# morseSounder.net
KiCad netlist of a schematic drawn in EAGLE
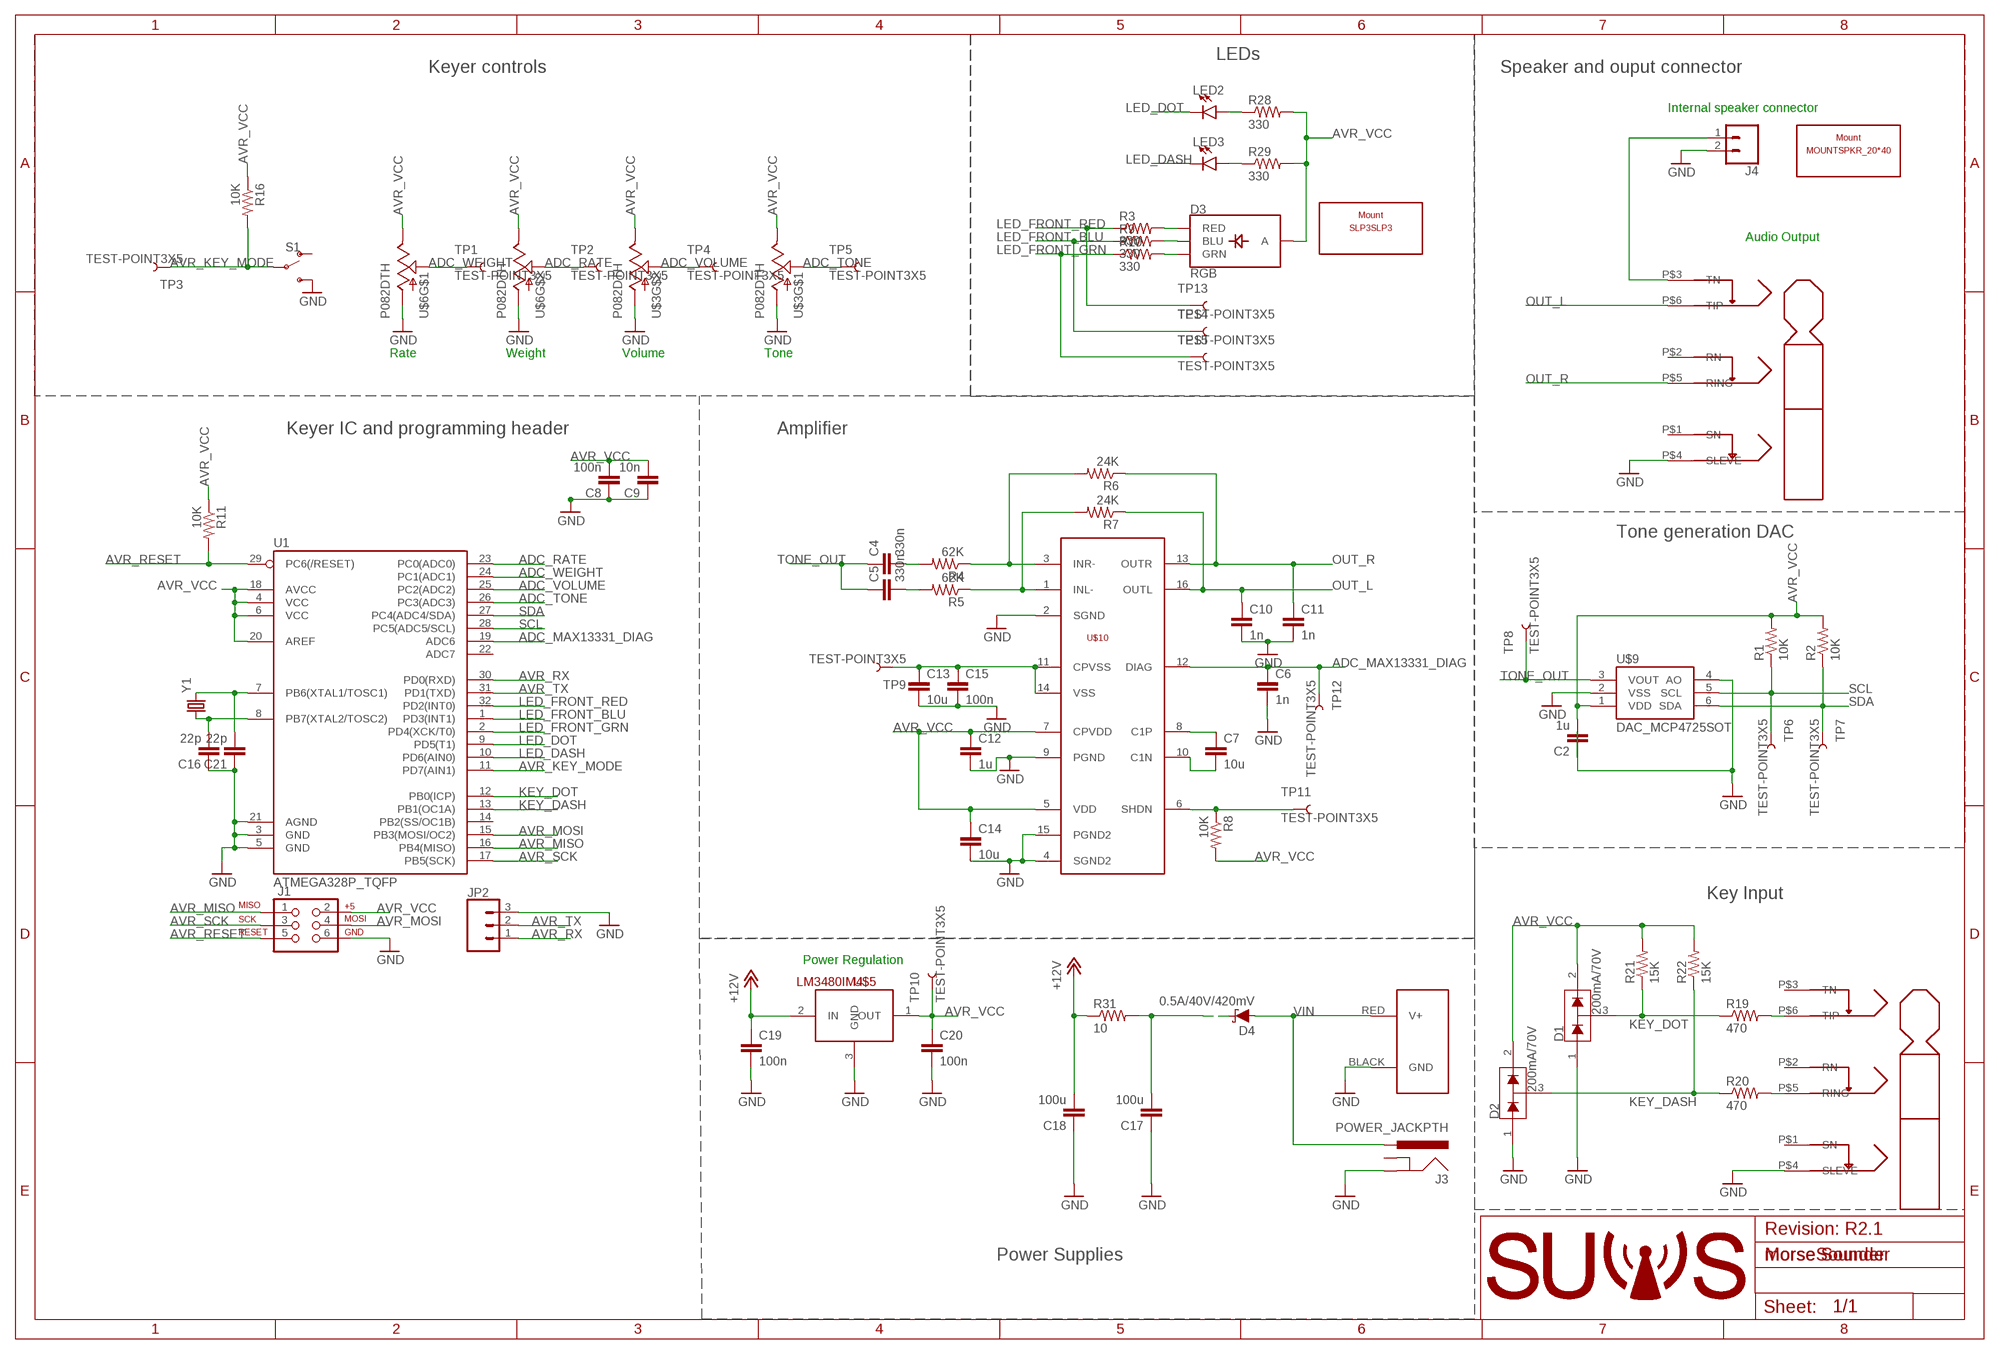
[diagram p0: schematic, sheet 1]

(export (version "E")
  (design (tool "Eeschema 10.0.6"))
  (components
    (comp (ref "C2")
      (value "1u")
      (footprint "eagle-import:0805")
      (libsource (lib "eagle-import") (part "CAP0805"))
    )
    (comp (ref "C4")
      (value "330n")
      (footprint "eagle-import:0805")
      (libsource (lib "eagle-import") (part "CAP0805"))
    )
    (comp (ref "C5")
      (value "330n")
      (footprint "eagle-import:0805")
      (libsource (lib "eagle-import") (part "CAP0805"))
    )
    (comp (ref "C6")
      (value "1n")
      (footprint "eagle-import:0805")
      (libsource (lib "eagle-import") (part "CAP0805"))
    )
    (comp (ref "C7")
      (value "10u")
      (footprint "eagle-import:0805")
      (libsource (lib "eagle-import") (part "CAP0805"))
    )
    (comp (ref "C8")
      (value "100n")
      (footprint "eagle-import:0805")
      (libsource (lib "eagle-import") (part "CAP0805"))
    )
    (comp (ref "C9")
      (value "10n")
      (footprint "eagle-import:0805")
      (libsource (lib "eagle-import") (part "CAP0805"))
    )
    (comp (ref "C10")
      (value "1n")
      (footprint "eagle-import:0805")
      (libsource (lib "eagle-import") (part "CAP0805"))
    )
    (comp (ref "C11")
      (value "1n")
      (footprint "eagle-import:0805")
      (libsource (lib "eagle-import") (part "CAP0805"))
    )
    (comp (ref "C12")
      (value "1u")
      (footprint "eagle-import:0805")
      (libsource (lib "eagle-import") (part "CAP0805"))
    )
    (comp (ref "C13")
      (value "10u")
      (footprint "eagle-import:0805")
      (libsource (lib "eagle-import") (part "CAP0805"))
    )
    (comp (ref "C14")
      (value "10u")
      (footprint "eagle-import:0805")
      (libsource (lib "eagle-import") (part "CAP0805"))
    )
    (comp (ref "C15")
      (value "100n")
      (footprint "eagle-import:0805")
      (libsource (lib "eagle-import") (part "CAP0805"))
    )
    (comp (ref "C16")
      (value "22p")
      (footprint "eagle-import:0805")
      (libsource (lib "eagle-import") (part "CAP0805"))
    )
    (comp (ref "C17")
      (value "100u")
      (footprint "eagle-import:0805")
      (libsource (lib "eagle-import") (part "CAP0805"))
    )
    (comp (ref "C18")
      (value "100u")
      (footprint "eagle-import:0805")
      (libsource (lib "eagle-import") (part "CAP0805"))
    )
    (comp (ref "C19")
      (value "100n")
      (footprint "eagle-import:0805")
      (libsource (lib "eagle-import") (part "CAP0805"))
    )
    (comp (ref "C20")
      (value "100n")
      (footprint "eagle-import:0805")
      (libsource (lib "eagle-import") (part "CAP0805"))
    )
    (comp (ref "C21")
      (value "22p")
      (footprint "eagle-import:0805")
      (libsource (lib "eagle-import") (part "CAP0805"))
    )
    (comp (ref "D1")
      (value "200mA/70V")
      (footprint "eagle-import:SOT23-3")
      (libsource (lib "eagle-import") (part "BAV99"))
    )
    (comp (ref "D2")
      (value "200mA/70V")
      (footprint "eagle-import:SOT23-3")
      (libsource (lib "eagle-import") (part "BAV99"))
    )
    (comp (ref "D3")
      (value "RGB")
      (footprint "eagle-import:P-LCC-4-3")
      (libsource (lib "eagle-import") (part "LED-RGB-CACREE"))
    )
    (comp (ref "D4")
      (value "0.5A/40V/420mV")
      (footprint "eagle-import:SOD-323")
      (libsource (lib "eagle-import") (part "DIODE-SCHOTTKY-PMEG4005EJ"))
    )
    (comp (ref "J1")
      (value "AVR_SPI_PRG_6PTH")
      (footprint "eagle-import:2X3")
      (libsource (lib "eagle-import") (part "AVR_SPI_PRG_6PTH"))
    )
    (comp (ref "J2")
      (value "POWERPOLE_POWER25A_HORIZONTAL_G2")
      (footprint "eagle-import:POWERPOLE_PAIR_25A_HORIZ_G2")
      (libsource (lib "eagle-import") (part "POWERPOLE_POWER25A_HORIZONTAL_G2"))
    )
    (comp (ref "J3")
      (value "POWER_JACKPTH")
      (footprint "eagle-import:POWER_JACK_PTH")
      (libsource (lib "eagle-import") (part "POWER_JACKPTH"))
    )
    (comp (ref "J4")
      (value "CONN_02")
      (footprint "eagle-import:1X02")
      (libsource (lib "eagle-import") (part "CONN_02"))
    )
    (comp (ref "JP2")
      (value "CONN_03")
      (footprint "eagle-import:1X03")
      (libsource (lib "eagle-import") (part "CONN_03"))
    )
    (comp (ref "LED2")
      (value "LED-RED1206")
      (footprint "eagle-import:LED-1206")
      (libsource (lib "eagle-import") (part "LED-RED1206"))
    )
    (comp (ref "LED3")
      (value "LED-RED1206")
      (footprint "eagle-import:LED-1206")
      (libsource (lib "eagle-import") (part "LED-RED1206"))
    )
    (comp (ref "R1")
      (value "10K")
      (footprint "eagle-import:0805")
      (libsource (lib "eagle-import") (part "RESISTOR0805-RES"))
    )
    (comp (ref "R2")
      (value "10K")
      (footprint "eagle-import:0805")
      (libsource (lib "eagle-import") (part "RESISTOR0805-RES"))
    )
    (comp (ref "R3")
      (value "330")
      (footprint "eagle-import:0805")
      (libsource (lib "eagle-import") (part "RESISTOR0805-RES"))
    )
    (comp (ref "R4")
      (value "62K")
      (footprint "eagle-import:0805")
      (libsource (lib "eagle-import") (part "RESISTOR0805-RES"))
    )
    (comp (ref "R5")
      (value "62K")
      (footprint "eagle-import:0805")
      (libsource (lib "eagle-import") (part "RESISTOR0805-RES"))
    )
    (comp (ref "R6")
      (value "24K")
      (footprint "eagle-import:0805")
      (libsource (lib "eagle-import") (part "RESISTOR0805-RES"))
    )
    (comp (ref "R7")
      (value "24K")
      (footprint "eagle-import:0805")
      (libsource (lib "eagle-import") (part "RESISTOR0805-RES"))
    )
    (comp (ref "R8")
      (value "10K")
      (footprint "eagle-import:0805")
      (libsource (lib "eagle-import") (part "RESISTOR0805-RES"))
    )
    (comp (ref "R9")
      (value "330")
      (footprint "eagle-import:0805")
      (libsource (lib "eagle-import") (part "RESISTOR0805-RES"))
    )
    (comp (ref "R10")
      (value "330")
      (footprint "eagle-import:0805")
      (libsource (lib "eagle-import") (part "RESISTOR0805-RES"))
    )
    (comp (ref "R11")
      (value "10K")
      (footprint "eagle-import:0805")
      (libsource (lib "eagle-import") (part "RESISTOR0805-RES"))
    )
    (comp (ref "R16")
      (value "10K")
      (footprint "eagle-import:0805")
      (libsource (lib "eagle-import") (part "RESISTOR0805-RES"))
    )
    (comp (ref "R19")
      (value "470")
      (footprint "eagle-import:0805")
      (libsource (lib "eagle-import") (part "RESISTOR0805-RES"))
    )
    (comp (ref "R20")
      (value "470")
      (footprint "eagle-import:0805")
      (libsource (lib "eagle-import") (part "RESISTOR0805-RES"))
    )
    (comp (ref "R21")
      (value "15K")
      (footprint "eagle-import:0805")
      (libsource (lib "eagle-import") (part "RESISTOR0805-RES"))
    )
    (comp (ref "R22")
      (value "15K")
      (footprint "eagle-import:0805")
      (libsource (lib "eagle-import") (part "RESISTOR0805-RES"))
    )
    (comp (ref "R28")
      (value "330")
      (footprint "eagle-import:0805")
      (libsource (lib "eagle-import") (part "RESISTOR0805-RES"))
    )
    (comp (ref "R29")
      (value "330")
      (footprint "eagle-import:0805")
      (libsource (lib "eagle-import") (part "RESISTOR0805-RES"))
    )
    (comp (ref "R31")
      (value "10")
      (footprint "eagle-import:0805")
      (libsource (lib "eagle-import") (part "RESISTOR0805-RES"))
    )
    (comp (ref "S1")
      (value "SWITCH-SPDTTE-1825232-1")
      (footprint "eagle-import:TE-1825232-1")
      (libsource (lib "eagle-import") (part "SWITCH-SPDTTE-1825232-1"))
    )
    (comp (ref "TP1")
      (value "TEST-POINT3X5")
      (footprint "eagle-import:PAD.03X.05")
      (libsource (lib "eagle-import") (part "TEST-POINT3X5"))
    )
    (comp (ref "TP2")
      (value "TEST-POINT3X5")
      (footprint "eagle-import:PAD.03X.05")
      (libsource (lib "eagle-import") (part "TEST-POINT3X5"))
    )
    (comp (ref "TP3")
      (value "TEST-POINT3X5")
      (footprint "eagle-import:PAD.03X.05")
      (libsource (lib "eagle-import") (part "TEST-POINT3X5"))
    )
    (comp (ref "TP4")
      (value "TEST-POINT3X5")
      (footprint "eagle-import:PAD.03X.05")
      (libsource (lib "eagle-import") (part "TEST-POINT3X5"))
    )
    (comp (ref "TP5")
      (value "TEST-POINT3X5")
      (footprint "eagle-import:PAD.03X.05")
      (libsource (lib "eagle-import") (part "TEST-POINT3X5"))
    )
    (comp (ref "TP6")
      (value "TEST-POINT3X5")
      (footprint "eagle-import:PAD.03X.05")
      (libsource (lib "eagle-import") (part "TEST-POINT3X5"))
    )
    (comp (ref "TP7")
      (value "TEST-POINT3X5")
      (footprint "eagle-import:PAD.03X.05")
      (libsource (lib "eagle-import") (part "TEST-POINT3X5"))
    )
    (comp (ref "TP8")
      (value "TEST-POINT3X5")
      (footprint "eagle-import:PAD.03X.05")
      (libsource (lib "eagle-import") (part "TEST-POINT3X5"))
    )
    (comp (ref "TP9")
      (value "TEST-POINT3X5")
      (footprint "eagle-import:PAD.03X.05")
      (libsource (lib "eagle-import") (part "TEST-POINT3X5"))
    )
    (comp (ref "TP10")
      (value "TEST-POINT3X5")
      (footprint "eagle-import:PAD.03X.05")
      (libsource (lib "eagle-import") (part "TEST-POINT3X5"))
    )
    (comp (ref "TP11")
      (value "TEST-POINT3X5")
      (footprint "eagle-import:PAD.03X.05")
      (libsource (lib "eagle-import") (part "TEST-POINT3X5"))
    )
    (comp (ref "TP12")
      (value "TEST-POINT3X5")
      (footprint "eagle-import:PAD.03X.05")
      (libsource (lib "eagle-import") (part "TEST-POINT3X5"))
    )
    (comp (ref "TP13")
      (value "TEST-POINT3X5")
      (footprint "eagle-import:PAD.03X.05")
      (libsource (lib "eagle-import") (part "TEST-POINT3X5"))
    )
    (comp (ref "TP14")
      (value "TEST-POINT3X5")
      (footprint "eagle-import:PAD.03X.05")
      (libsource (lib "eagle-import") (part "TEST-POINT3X5"))
    )
    (comp (ref "TP15")
      (value "TEST-POINT3X5")
      (footprint "eagle-import:PAD.03X.05")
      (libsource (lib "eagle-import") (part "TEST-POINT3X5"))
    )
    (comp (ref "U$1")
      (value "NRJ6HH")
      (footprint "eagle-import:NRJ6HH")
      (libsource (lib "eagle-import") (part "NRJ6HH"))
    )
    (comp (ref "U$2")
      (value "NRJ6HH")
      (footprint "eagle-import:NRJ6HH")
      (libsource (lib "eagle-import") (part "NRJ6HH"))
    )
    (comp (ref "U$3")
      (value "P082DTH")
      (footprint "eagle-import:P082D")
      (libsource (lib "eagle-import") (part "P082DTH"))
    )
    (comp (ref "U$4")
      (value "MOUNTSPKR_20*40")
      (footprint "eagle-import:SKR_MNT")
      (libsource (lib "eagle-import") (part "MOUNTSPKR_2040"))
    )
    (comp (ref "U$5")
      (value "LM3480IM4")
      (footprint "eagle-import:SOT23-3")
      (libsource (lib "eagle-import") (part "LM3480IM4"))
    )
    (comp (ref "U$6")
      (value "P082DTH")
      (footprint "eagle-import:P082D")
      (libsource (lib "eagle-import") (part "P082DTH"))
    )
    (comp (ref "U$7")
      (value "LOGO_SUWSLOGO_LARGE")
      (footprint "eagle-import:LOGO_SUWS")
      (libsource (lib "eagle-import") (part "LOGO_SUWSLOGO_LARGE"))
    )
    (comp (ref "U$8")
      (value "SLP3SLP3")
      (footprint "eagle-import:SLP-3")
      (libsource (lib "eagle-import") (part "SLP3SLP3"))
    )
    (comp (ref "U$9")
      (value "DAC_MCP4725SOT")
      (footprint "eagle-import:SOT23-6")
      (libsource (lib "eagle-import") (part "DAC_MCP4725SOT"))
    )
    (comp (ref "U$10")
      (value "MAX13331")
      (footprint "eagle-import:SSOP16")
      (libsource (lib "eagle-import") (part "MAX13331"))
    )
    (comp (ref "U1")
      (value "ATMEGA328P_TQFP")
      (footprint "eagle-import:TQFP32-08")
      (libsource (lib "eagle-import") (part "ATMEGA328P_TQFP"))
    )
    (comp (ref "Y1")
      (value "CRYSTALHC49UV")
      (footprint "eagle-import:HC49U-V")
      (libsource (lib "eagle-import") (part "CRYSTALHC49UV"))
    )
  )
  (nets
    (net (code "1") (name "+12V") (class "Default")
      (node (ref "C18") (pin "2") (pinfunction "2_2") (pintype "passive"))
      (node (ref "C19") (pin "1") (pinfunction "1_1") (pintype "passive"))
      (node (ref "R31") (pin "1") (pinfunction "1_1") (pintype "passive"))
      (node (ref "U$5") (pin "2") (pinfunction "IN_2") (pintype "bidirectional"))
    )
    (net (code "2") (name "/ADC_MAX13331_DIAG") (class "Default")
      (node (ref "C6") (pin "1") (pinfunction "1_1") (pintype "passive"))
      (node (ref "TP12") (pin "P$1") (pinfunction "1_P$1") (pintype "bidirectional"))
      (node (ref "U$10") (pin "12") (pinfunction "DIAG_12") (pintype "bidirectional"))
      (node (ref "U1") (pin "19") (pinfunction "ADC6_19") (pintype "bidirectional"))
    )
    (net (code "3") (name "/ADC_RATE") (class "Default")
      (node (ref "TP2") (pin "P$1") (pinfunction "1_P$1") (pintype "bidirectional"))
      (node (ref "U$6") (pin "R2") (pinfunction "S_R2") (pintype "passive"))
      (node (ref "U1") (pin "23") (pinfunction "PC0(ADC0)_23") (pintype "bidirectional"))
    )
    (net (code "4") (name "/ADC_TONE") (class "Default")
      (node (ref "TP5") (pin "P$1") (pinfunction "1_P$1") (pintype "bidirectional"))
      (node (ref "U$3") (pin "F2") (pinfunction "S_F2") (pintype "passive"))
      (node (ref "U1") (pin "26") (pinfunction "PC3(ADC3)_26") (pintype "bidirectional"))
    )
    (net (code "5") (name "/ADC_VOLUME") (class "Default")
      (node (ref "TP4") (pin "P$1") (pinfunction "1_P$1") (pintype "bidirectional"))
      (node (ref "U$3") (pin "R2") (pinfunction "S_R2") (pintype "passive"))
      (node (ref "U1") (pin "25") (pinfunction "PC2(ADC2)_25") (pintype "bidirectional"))
    )
    (net (code "6") (name "/ADC_WEIGHT") (class "Default")
      (node (ref "TP1") (pin "P$1") (pinfunction "1_P$1") (pintype "bidirectional"))
      (node (ref "U$6") (pin "F2") (pinfunction "S_F2") (pintype "passive"))
      (node (ref "U1") (pin "24") (pinfunction "PC1(ADC1)_24") (pintype "bidirectional"))
    )
    (net (code "7") (name "/AVR_KEY_MODE") (class "Default")
      (node (ref "R16") (pin "2") (pinfunction "2_2") (pintype "passive"))
      (node (ref "S1") (pin "2") (pinfunction "P_2") (pintype "passive"))
      (node (ref "TP3") (pin "P$1") (pinfunction "1_P$1") (pintype "bidirectional"))
      (node (ref "U1") (pin "11") (pinfunction "PD7(AIN1)_11") (pintype "bidirectional"))
    )
    (net (code "8") (name "/AVR_MISO") (class "Default")
      (node (ref "J1") (pin "1") (pinfunction "1_1") (pintype "passive"))
      (node (ref "U1") (pin "16") (pinfunction "PB4(MISO)_16") (pintype "bidirectional"))
    )
    (net (code "9") (name "/AVR_MOSI") (class "Default")
      (node (ref "J1") (pin "4") (pinfunction "4_4") (pintype "passive"))
      (node (ref "U1") (pin "15") (pinfunction "PB3(MOSI/OC2)_15") (pintype "bidirectional"))
    )
    (net (code "10") (name "/AVR_RESET") (class "Default")
      (node (ref "J1") (pin "5") (pinfunction "5_5") (pintype "passive"))
      (node (ref "R11") (pin "2") (pinfunction "2_2") (pintype "passive"))
      (node (ref "U1") (pin "29") (pinfunction "PC6(/RESET)_29") (pintype "bidirectional"))
    )
    (net (code "11") (name "/AVR_RX") (class "Default")
      (node (ref "JP2") (pin "1") (pinfunction "1_1") (pintype "passive"))
      (node (ref "U1") (pin "30") (pinfunction "PD0(RXD)_30") (pintype "bidirectional"))
    )
    (net (code "12") (name "/AVR_SCK") (class "Default")
      (node (ref "J1") (pin "3") (pinfunction "3_3") (pintype "passive"))
      (node (ref "U1") (pin "17") (pinfunction "PB5(SCK)_17") (pintype "bidirectional"))
    )
    (net (code "13") (name "/AVR_TX") (class "Default")
      (node (ref "JP2") (pin "2") (pinfunction "2_2") (pintype "passive"))
      (node (ref "U1") (pin "31") (pinfunction "PD1(TXD)_31") (pintype "bidirectional"))
    )
    (net (code "14") (name "/AVR_VCC") (class "Default")
      (node (ref "C12") (pin "1") (pinfunction "1_1") (pintype "passive"))
      (node (ref "C14") (pin "1") (pinfunction "1_1") (pintype "passive"))
      (node (ref "C2") (pin "2") (pinfunction "2_2") (pintype "passive"))
      (node (ref "C20") (pin "1") (pinfunction "1_1") (pintype "passive"))
      (node (ref "C8") (pin "2") (pinfunction "2_2") (pintype "passive"))
      (node (ref "C9") (pin "2") (pinfunction "2_2") (pintype "passive"))
      (node (ref "D1") (pin "2") (pinfunction "C2_2") (pintype "bidirectional"))
      (node (ref "D2") (pin "2") (pinfunction "C2_2") (pintype "bidirectional"))
      (node (ref "D3") (pin "1") (pinfunction "A_1") (pintype "bidirectional"))
      (node (ref "J1") (pin "2") (pinfunction "2_2") (pintype "passive"))
      (node (ref "R1") (pin "2") (pinfunction "2_2") (pintype "passive"))
      (node (ref "R11") (pin "1") (pinfunction "1_1") (pintype "passive"))
      (node (ref "R16") (pin "1") (pinfunction "1_1") (pintype "passive"))
      (node (ref "R2") (pin "2") (pinfunction "2_2") (pintype "passive"))
      (node (ref "R21") (pin "2") (pinfunction "2_2") (pintype "passive"))
      (node (ref "R22") (pin "2") (pinfunction "2_2") (pintype "passive"))
      (node (ref "R28") (pin "2") (pinfunction "2_2") (pintype "passive"))
      (node (ref "R29") (pin "2") (pinfunction "2_2") (pintype "passive"))
      (node (ref "R8") (pin "2") (pinfunction "2_2") (pintype "passive"))
      (node (ref "TP10") (pin "P$1") (pinfunction "1_P$1") (pintype "bidirectional"))
      (node (ref "U$10") (pin "5") (pinfunction "VDD_5") (pintype "bidirectional"))
      (node (ref "U$10") (pin "7") (pinfunction "CPVDD_7") (pintype "bidirectional"))
      (node (ref "U$3") (pin "F3") (pinfunction "E_F3") (pintype "passive"))
      (node (ref "U$3") (pin "R3") (pinfunction "E_R3") (pintype "passive"))
      (node (ref "U$5") (pin "1") (pinfunction "OUT_1") (pintype "bidirectional"))
      (node (ref "U$6") (pin "F3") (pinfunction "E_F3") (pintype "passive"))
      (node (ref "U$6") (pin "R3") (pinfunction "E_R3") (pintype "passive"))
      (node (ref "U$9") (pin "1") (pinfunction "VDD_1") (pintype "bidirectional"))
      (node (ref "U1") (pin "18") (pinfunction "AVCC_18") (pintype "bidirectional"))
      (node (ref "U1") (pin "20") (pinfunction "AREF_20") (pintype "bidirectional"))
      (node (ref "U1") (pin "4") (pinfunction "VCC_4") (pintype "bidirectional"))
      (node (ref "U1") (pin "6") (pinfunction "VCC_6") (pintype "bidirectional"))
    )
    (net (code "15") (name "/KEY_DASH") (class "Default")
      (node (ref "D2") (pin "3") (pinfunction "COM_3") (pintype "bidirectional"))
      (node (ref "R20") (pin "1") (pinfunction "1_1") (pintype "passive"))
      (node (ref "R22") (pin "1") (pinfunction "1_1") (pintype "passive"))
      (node (ref "U1") (pin "13") (pinfunction "PB1(OC1A)_13") (pintype "bidirectional"))
    )
    (net (code "16") (name "/KEY_DOT") (class "Default")
      (node (ref "D1") (pin "3") (pinfunction "COM_3") (pintype "bidirectional"))
      (node (ref "R19") (pin "1") (pinfunction "1_1") (pintype "passive"))
      (node (ref "R21") (pin "1") (pinfunction "1_1") (pintype "passive"))
      (node (ref "U1") (pin "12") (pinfunction "PB0(ICP)_12") (pintype "bidirectional"))
    )
    (net (code "17") (name "/LED_DASH") (class "Default")
      (node (ref "LED3") (pin "C") (pinfunction "C_C") (pintype "passive"))
      (node (ref "U1") (pin "10") (pinfunction "PD6(AIN0)_10") (pintype "bidirectional"))
    )
    (net (code "18") (name "/LED_DOT") (class "Default")
      (node (ref "LED2") (pin "C") (pinfunction "C_C") (pintype "passive"))
      (node (ref "U1") (pin "9") (pinfunction "PD5(T1)_9") (pintype "bidirectional"))
    )
    (net (code "19") (name "/LED_FRONT_BLU") (class "Default")
      (node (ref "R9") (pin "1") (pinfunction "1_1") (pintype "passive"))
      (node (ref "TP14") (pin "P$1") (pinfunction "1_P$1") (pintype "bidirectional"))
      (node (ref "U1") (pin "1") (pinfunction "PD3(INT1)_1") (pintype "bidirectional"))
    )
    (net (code "20") (name "/LED_FRONT_GRN") (class "Default")
      (node (ref "R10") (pin "1") (pinfunction "1_1") (pintype "passive"))
      (node (ref "TP15") (pin "P$1") (pinfunction "1_P$1") (pintype "bidirectional"))
      (node (ref "U1") (pin "2") (pinfunction "PD4(XCK/T0)_2") (pintype "bidirectional"))
    )
    (net (code "21") (name "/LED_FRONT_RED") (class "Default")
      (node (ref "R3") (pin "1") (pinfunction "1_1") (pintype "passive"))
      (node (ref "TP13") (pin "P$1") (pinfunction "1_P$1") (pintype "bidirectional"))
      (node (ref "U1") (pin "32") (pinfunction "PD2(INT0)_32") (pintype "bidirectional"))
    )
    (net (code "22") (name "/OUT_L") (class "Default")
      (node (ref "C10") (pin "1") (pinfunction "1_1") (pintype "passive"))
      (node (ref "R7") (pin "1") (pinfunction "1_1") (pintype "passive"))
      (node (ref "U$10") (pin "16") (pinfunction "OUTL_16") (pintype "bidirectional"))
      (node (ref "U$2") (pin "P$6") (pinfunction "TIP_P$6") (pintype "bidirectional"))
    )
    (net (code "23") (name "/OUT_R") (class "Default")
      (node (ref "C11") (pin "1") (pinfunction "1_1") (pintype "passive"))
      (node (ref "R6") (pin "1") (pinfunction "1_1") (pintype "passive"))
      (node (ref "U$10") (pin "13") (pinfunction "OUTR_13") (pintype "bidirectional"))
      (node (ref "U$2") (pin "P$5") (pinfunction "RING_P$5") (pintype "bidirectional"))
    )
    (net (code "24") (name "/SCL") (class "Default")
      (node (ref "R1") (pin "1") (pinfunction "1_1") (pintype "passive"))
      (node (ref "TP6") (pin "P$1") (pinfunction "1_P$1") (pintype "bidirectional"))
      (node (ref "U$9") (pin "5") (pinfunction "SCL_5") (pintype "bidirectional"))
      (node (ref "U1") (pin "28") (pinfunction "PC5(ADC5/SCL)_28") (pintype "bidirectional"))
    )
    (net (code "25") (name "/SDA") (class "Default")
      (node (ref "R2") (pin "1") (pinfunction "1_1") (pintype "passive"))
      (node (ref "TP7") (pin "P$1") (pinfunction "1_P$1") (pintype "bidirectional"))
      (node (ref "U$9") (pin "6") (pinfunction "SDA_6") (pintype "bidirectional"))
      (node (ref "U1") (pin "27") (pinfunction "PC4(ADC4/SDA)_27") (pintype "bidirectional"))
    )
    (net (code "26") (name "/TONE_OUT") (class "Default")
      (node (ref "C4") (pin "1") (pinfunction "1_1") (pintype "passive"))
      (node (ref "C5") (pin "1") (pinfunction "1_1") (pintype "passive"))
      (node (ref "TP8") (pin "P$1") (pinfunction "1_P$1") (pintype "bidirectional"))
      (node (ref "U$9") (pin "3") (pinfunction "VOUT_3") (pintype "bidirectional"))
    )
    (net (code "27") (name "/VIN") (class "Default")
      (node (ref "D4") (pin "A") (pinfunction "A_A") (pintype "passive"))
      (node (ref "J2") (pin "RED") (pinfunction "V+_RED") (pintype "power_in"))
      (node (ref "J3") (pin "PWR") (pinfunction "PWR_PWR") (pintype "bidirectional"))
    )
    (net (code "28") (name "GND") (class "Default")
      (node (ref "C10") (pin "2") (pinfunction "2_2") (pintype "passive"))
      (node (ref "C11") (pin "2") (pinfunction "2_2") (pintype "passive"))
      (node (ref "C12") (pin "2") (pinfunction "2_2") (pintype "passive"))
      (node (ref "C13") (pin "2") (pinfunction "2_2") (pintype "passive"))
      (node (ref "C14") (pin "2") (pinfunction "2_2") (pintype "passive"))
      (node (ref "C15") (pin "2") (pinfunction "2_2") (pintype "passive"))
      (node (ref "C16") (pin "1") (pinfunction "1_1") (pintype "passive"))
      (node (ref "C17") (pin "1") (pinfunction "1_1") (pintype "passive"))
      (node (ref "C18") (pin "1") (pinfunction "1_1") (pintype "passive"))
      (node (ref "C19") (pin "2") (pinfunction "2_2") (pintype "passive"))
      (node (ref "C2") (pin "1") (pinfunction "1_1") (pintype "passive"))
      (node (ref "C20") (pin "2") (pinfunction "2_2") (pintype "passive"))
      (node (ref "C21") (pin "1") (pinfunction "1_1") (pintype "passive"))
      (node (ref "C6") (pin "2") (pinfunction "2_2") (pintype "passive"))
      (node (ref "C8") (pin "1") (pinfunction "1_1") (pintype "passive"))
      (node (ref "C9") (pin "1") (pinfunction "1_1") (pintype "passive"))
      (node (ref "D1") (pin "1") (pinfunction "A1_1") (pintype "bidirectional"))
      (node (ref "D2") (pin "1") (pinfunction "A1_1") (pintype "bidirectional"))
      (node (ref "J1") (pin "6") (pinfunction "6_6") (pintype "passive"))
      (node (ref "J2") (pin "BLACK") (pinfunction "GND_BLACK") (pintype "power_in"))
      (node (ref "J3") (pin "GND") (pinfunction "GND_GND") (pintype "bidirectional"))
      (node (ref "J4") (pin "2") (pinfunction "2_2") (pintype "passive"))
      (node (ref "JP2") (pin "3") (pinfunction "3_3") (pintype "passive"))
      (node (ref "S1") (pin "3") (pinfunction "S_3") (pintype "passive"))
      (node (ref "U$1") (pin "P$4") (pinfunction "SLEVE_P$4") (pintype "bidirectional"))
      (node (ref "U$10") (pin "15") (pinfunction "PGND2_15") (pintype "bidirectional"))
      (node (ref "U$10") (pin "2") (pinfunction "SGND_2") (pintype "bidirectional"))
      (node (ref "U$10") (pin "4") (pinfunction "SGND2_4") (pintype "bidirectional"))
      (node (ref "U$10") (pin "9") (pinfunction "PGND_9") (pintype "bidirectional"))
      (node (ref "U$2") (pin "P$4") (pinfunction "SLEVE_P$4") (pintype "bidirectional"))
      (node (ref "U$3") (pin "F1") (pinfunction "A_F1") (pintype "passive"))
      (node (ref "U$3") (pin "R1") (pinfunction "A_R1") (pintype "passive"))
      (node (ref "U$5") (pin "3") (pinfunction "GND_3") (pintype "bidirectional"))
      (node (ref "U$6") (pin "F1") (pinfunction "A_F1") (pintype "passive"))
      (node (ref "U$6") (pin "R1") (pinfunction "A_R1") (pintype "passive"))
      (node (ref "U$9") (pin "2") (pinfunction "VSS_2") (pintype "bidirectional"))
      (node (ref "U$9") (pin "4") (pinfunction "AO_4") (pintype "bidirectional"))
      (node (ref "U1") (pin "21") (pinfunction "AGND_21") (pintype "bidirectional"))
      (node (ref "U1") (pin "3") (pinfunction "GND_3") (pintype "bidirectional"))
      (node (ref "U1") (pin "5") (pinfunction "GND_5") (pintype "bidirectional"))
    )
    (net (code "29") (name "Net-(C4-Pad2)") (class "Default")
      (node (ref "C4") (pin "2") (pinfunction "2_2") (pintype "passive"))
      (node (ref "R4") (pin "2") (pinfunction "2_2") (pintype "passive"))
    )
    (net (code "30") (name "Net-(C5-Pad2)") (class "Default")
      (node (ref "C5") (pin "2") (pinfunction "2_2") (pintype "passive"))
      (node (ref "R5") (pin "2") (pinfunction "2_2") (pintype "passive"))
    )
    (net (code "31") (name "Net-(C17-Pad2)") (class "Default")
      (node (ref "C17") (pin "2") (pinfunction "2_2") (pintype "passive"))
      (node (ref "D4") (pin "C") (pinfunction "C_C") (pintype "passive"))
      (node (ref "R31") (pin "2") (pinfunction "2_2") (pintype "passive"))
    )
    (net (code "32") (name "Net-(D3-BLU)") (class "Default")
      (node (ref "D3") (pin "4") (pinfunction "BLU_4") (pintype "bidirectional"))
      (node (ref "R9") (pin "2") (pinfunction "2_2") (pintype "passive"))
    )
    (net (code "33") (name "Net-(D3-GRN)") (class "Default")
      (node (ref "D3") (pin "3") (pinfunction "GRN_3") (pintype "bidirectional"))
      (node (ref "R10") (pin "2") (pinfunction "2_2") (pintype "passive"))
    )
    (net (code "34") (name "Net-(D3-RED)") (class "Default")
      (node (ref "D3") (pin "2") (pinfunction "RED_2") (pintype "bidirectional"))
      (node (ref "R3") (pin "2") (pinfunction "2_2") (pintype "passive"))
    )
    (net (code "35") (name "Net-(LED2-PadA)") (class "Default")
      (node (ref "LED2") (pin "A") (pinfunction "A_A") (pintype "passive"))
      (node (ref "R28") (pin "1") (pinfunction "1_1") (pintype "passive"))
    )
    (net (code "36") (name "Net-(LED3-PadA)") (class "Default")
      (node (ref "LED3") (pin "A") (pinfunction "A_A") (pintype "passive"))
      (node (ref "R29") (pin "1") (pinfunction "1_1") (pintype "passive"))
    )
    (net (code "37") (name "Net-(TP9-1)") (class "Default")
      (node (ref "C13") (pin "1") (pinfunction "1_1") (pintype "passive"))
      (node (ref "C15") (pin "1") (pinfunction "1_1") (pintype "passive"))
      (node (ref "TP9") (pin "P$1") (pinfunction "1_P$1") (pintype "bidirectional"))
      (node (ref "U$10") (pin "11") (pinfunction "CPVSS_11") (pintype "bidirectional"))
      (node (ref "U$10") (pin "14") (pinfunction "VSS_14") (pintype "bidirectional"))
    )
    (net (code "38") (name "Net-(TP11-1)") (class "Default")
      (node (ref "R8") (pin "1") (pinfunction "1_1") (pintype "passive"))
      (node (ref "TP11") (pin "P$1") (pinfunction "1_P$1") (pintype "bidirectional"))
      (node (ref "U$10") (pin "6") (pinfunction "SHDN_6") (pintype "bidirectional"))
    )
    (net (code "39") (name "Net-(U$1-RING)") (class "Default")
      (node (ref "R20") (pin "2") (pinfunction "2_2") (pintype "passive"))
      (node (ref "U$1") (pin "P$5") (pinfunction "RING_P$5") (pintype "bidirectional"))
    )
    (net (code "40") (name "Net-(U$1-TIP)") (class "Default")
      (node (ref "R19") (pin "2") (pinfunction "2_2") (pintype "passive"))
      (node (ref "U$1") (pin "P$6") (pinfunction "TIP_P$6") (pintype "bidirectional"))
    )
    (net (code "41") (name "Net-(U$2-TN)") (class "Default")
      (node (ref "J4") (pin "1") (pinfunction "1_1") (pintype "passive"))
      (node (ref "U$2") (pin "P$3") (pinfunction "TN_P$3") (pintype "bidirectional"))
    )
    (net (code "42") (name "Net-(U$10-C1N)") (class "Default")
      (node (ref "C7") (pin "2") (pinfunction "2_2") (pintype "passive"))
      (node (ref "U$10") (pin "10") (pinfunction "C1N_10") (pintype "bidirectional"))
    )
    (net (code "43") (name "Net-(U$10-C1P)") (class "Default")
      (node (ref "C7") (pin "1") (pinfunction "1_1") (pintype "passive"))
      (node (ref "U$10") (pin "8") (pinfunction "C1P_8") (pintype "bidirectional"))
    )
    (net (code "44") (name "Net-(U$10-INL-)") (class "Default")
      (node (ref "R5") (pin "1") (pinfunction "1_1") (pintype "passive"))
      (node (ref "R7") (pin "2") (pinfunction "2_2") (pintype "passive"))
      (node (ref "U$10") (pin "1") (pinfunction "INL-_1") (pintype "bidirectional"))
    )
    (net (code "45") (name "Net-(U$10-INR-)") (class "Default")
      (node (ref "R4") (pin "1") (pinfunction "1_1") (pintype "passive"))
      (node (ref "R6") (pin "2") (pinfunction "2_2") (pintype "passive"))
      (node (ref "U$10") (pin "3") (pinfunction "INR-_3") (pintype "bidirectional"))
    )
    (net (code "46") (name "Net-(U1-PB6(XTAL1{slash}TOSC1))") (class "Default")
      (node (ref "C21") (pin "2") (pinfunction "2_2") (pintype "passive"))
      (node (ref "U1") (pin "7") (pinfunction "PB6(XTAL1/TOSC1)_7") (pintype "bidirectional"))
      (node (ref "Y1") (pin "2") (pinfunction "2_2") (pintype "passive"))
    )
    (net (code "47") (name "Net-(U1-PB7(XTAL2{slash}TOSC2))") (class "Default")
      (node (ref "C16") (pin "2") (pinfunction "2_2") (pintype "passive"))
      (node (ref "U1") (pin "8") (pinfunction "PB7(XTAL2/TOSC2)_8") (pintype "bidirectional"))
      (node (ref "Y1") (pin "1") (pinfunction "1_1") (pintype "passive"))
    )
    (net (code "48") (name "unconnected-(J3-PadGNDBREAK)") (class "Default")
      (node (ref "J3") (pin "GNDBREAK") (pinfunction "GNDBREAK_GNDBREAK") (pintype "bidirectional"))
    )
    (net (code "49") (name "unconnected-(S1-O-Pad1)") (class "Default")
      (node (ref "S1") (pin "1") (pinfunction "O_1") (pintype "passive"))
    )
    (net (code "50") (name "unconnected-(U$1-RN-PadP$2)") (class "Default")
      (node (ref "U$1") (pin "P$2") (pinfunction "RN_P$2") (pintype "bidirectional"))
    )
    (net (code "51") (name "unconnected-(U$1-SN-PadP$1)") (class "Default")
      (node (ref "U$1") (pin "P$1") (pinfunction "SN_P$1") (pintype "bidirectional"))
    )
    (net (code "52") (name "unconnected-(U$1-TN-PadP$3)") (class "Default")
      (node (ref "U$1") (pin "P$3") (pinfunction "TN_P$3") (pintype "bidirectional"))
    )
    (net (code "53") (name "unconnected-(U$2-RN-PadP$2)") (class "Default")
      (node (ref "U$2") (pin "P$2") (pinfunction "RN_P$2") (pintype "bidirectional"))
    )
    (net (code "54") (name "unconnected-(U$2-SN-PadP$1)") (class "Default")
      (node (ref "U$2") (pin "P$1") (pinfunction "SN_P$1") (pintype "bidirectional"))
    )
    (net (code "55") (name "unconnected-(U1-ADC7-Pad22)") (class "Default")
      (node (ref "U1") (pin "22") (pinfunction "ADC7_22") (pintype "bidirectional"))
    )
    (net (code "56") (name "unconnected-(U1-PB2(SS{slash}OC1B)-Pad14)") (class "Default")
      (node (ref "U1") (pin "14") (pinfunction "PB2(SS/OC1B)_14") (pintype "bidirectional"))
    )
  )
)
